# receiver.net
KiCad netlist of a schematic drawn in EAGLE
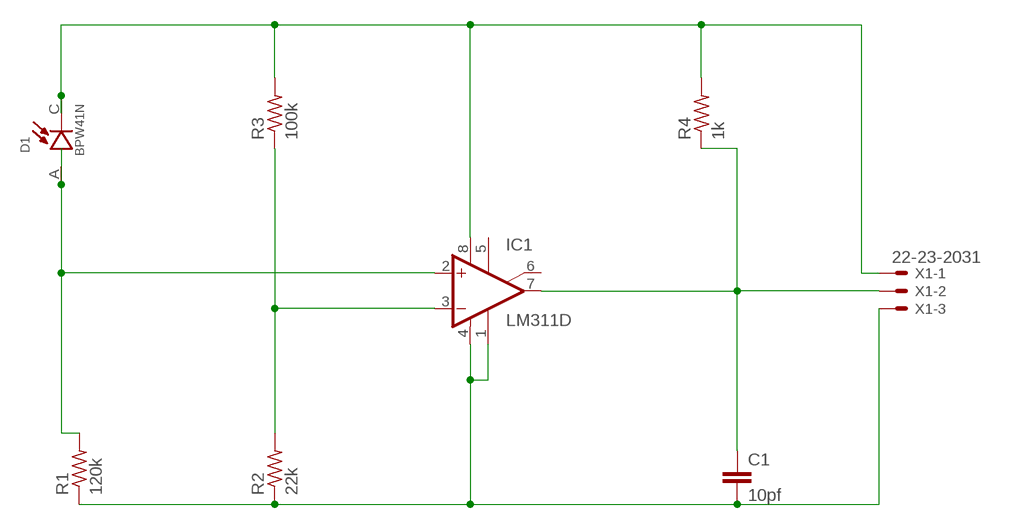
[diagram p0: schematic, sheet 1]

(export (version "E")
  (design (tool "Eeschema 10.0.6"))
  (components
    (comp (ref "C1")
      (value "10pf")
      (footprint "eagle-import:C2.5-2")
      (libsource (lib "eagle-import") (part "C2.5/2"))
    )
    (comp (ref "D1")
      (value "BPW41N")
      (footprint "eagle-import:DIO_BPW41N")
      (fields (field (name "MF") "Vishay Semiconductor Opto Division"))
      (libsource (lib "eagle-import") (part "BPW41N"))
    )
    (comp (ref "IC1")
      (value "LM311D")
      (footprint "eagle-import:SO08")
      (libsource (lib "eagle-import") (part "LM311D"))
    )
    (comp (ref "R1")
      (value "120k")
      (footprint "eagle-import:0207_10")
      (libsource (lib "eagle-import") (part "R-US_0207/10"))
    )
    (comp (ref "R2")
      (value "22k")
      (footprint "eagle-import:0207_10")
      (libsource (lib "eagle-import") (part "R-US_0207/10"))
    )
    (comp (ref "R3")
      (value "100k")
      (footprint "eagle-import:0207_10")
      (libsource (lib "eagle-import") (part "R-US_0207/10"))
    )
    (comp (ref "R4")
      (value "1k")
      (footprint "eagle-import:0207_10")
      (libsource (lib "eagle-import") (part "R-US_0207/10"))
    )
    (comp (ref "X1")
      (value "22-23-2031")
      (footprint "eagle-import:22-23-2031")
      (fields (field (name "MF") "MOLEX"))
      (libsource (lib "eagle-import") (part "22-23-2031"))
    )
  )
  (nets
    (net (code "1") (name "Net-(IC1-+IN)") (class "Default")
      (node (ref "D1") (pin "A") (pinfunction "A_A") (pintype "passive"))
      (node (ref "IC1") (pin "2") (pinfunction "+IN_2") (pintype "input"))
      (node (ref "R1") (pin "2") (pinfunction "2_2") (pintype "passive"))
    )
    (net (code "2") (name "Net-(IC1--IN)") (class "Default")
      (node (ref "IC1") (pin "3") (pinfunction "-IN_3") (pintype "input"))
      (node (ref "R2") (pin "2") (pinfunction "2_2") (pintype "passive"))
      (node (ref "R3") (pin "1") (pinfunction "1_1") (pintype "passive"))
    )
    (net (code "3") (name "Net-(IC1-GND)") (class "Default")
      (node (ref "C1") (pin "2") (pinfunction "2_2") (pintype "passive"))
      (node (ref "IC1") (pin "1") (pinfunction "GND_1") (pintype "passive"))
      (node (ref "IC1") (pin "4") (pinfunction "V-_4") (pintype "power_in"))
      (node (ref "R1") (pin "1") (pinfunction "1_1") (pintype "passive"))
      (node (ref "R2") (pin "1") (pinfunction "1_1") (pintype "passive"))
      (node (ref "X1") (pin "3") (pinfunction "S_3") (pintype "passive"))
    )
    (net (code "4") (name "Net-(IC1-OUT)") (class "Default")
      (node (ref "C1") (pin "1") (pinfunction "1_1") (pintype "passive"))
      (node (ref "IC1") (pin "7") (pinfunction "OUT_7") (pintype "output"))
      (node (ref "R4") (pin "1") (pinfunction "1_1") (pintype "passive"))
      (node (ref "X1") (pin "2") (pinfunction "S_2") (pintype "passive"))
    )
    (net (code "5") (name "Net-(IC1-V+)") (class "Default")
      (node (ref "D1") (pin "C") (pinfunction "C_C") (pintype "passive"))
      (node (ref "IC1") (pin "8") (pinfunction "V+_8") (pintype "power_in"))
      (node (ref "R3") (pin "2") (pinfunction "2_2") (pintype "passive"))
      (node (ref "R4") (pin "2") (pinfunction "2_2") (pintype "passive"))
      (node (ref "X1") (pin "1") (pinfunction "S_1") (pintype "passive"))
    )
    (net (code "6") (name "unconnected-(IC1-ON-Pad5)") (class "Default")
      (node (ref "IC1") (pin "5") (pinfunction "ON_5") (pintype "passive"))
    )
    (net (code "7") (name "unconnected-(IC1-ON{slash}STR-Pad6)") (class "Default")
      (node (ref "IC1") (pin "6") (pinfunction "ON/STR_6") (pintype "passive"))
    )
  )
)
